# RaspberryMicroSD.net
KiCad netlist of a schematic drawn in Altium Designer
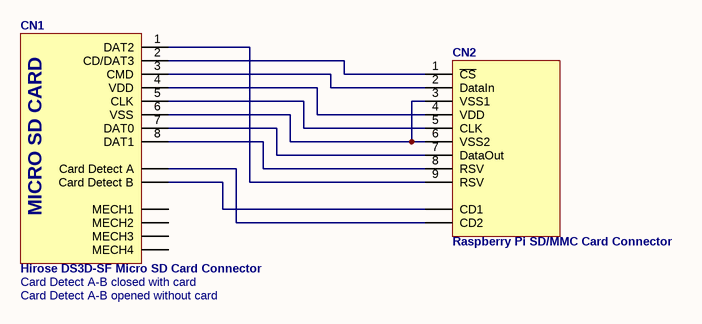
[diagram p0: RaspberryMicroSD.SchDoc]

(export (version "E")
  (design (tool "Eeschema 10.0.6"))
  (components
    (comp (ref "CN1")
      (value "Hirose DS3D-SF Micro SD Card Connector")
      (footprint "DM3D-SF")
      (description "DM3D Micro SD, Push-Pull (no ejection mechanism) Card Connector")
      (libsource (lib "data_cards") (part "DM3D-SF"))
    )
    (comp (ref "CN2")
      (value "Raspberry Pi SD/MMC Card Connector")
      (footprint "PCBComponent_1")
      (description "SD/MMC Card Connector")
      (libsource (lib "data_cards") (part "SD/MMC_1"))
    )
  )
  (nets
    (net (code "1") (name "Net-(CN1-CD{slash}DAT3)") (class "Default")
      (node (ref "CN1") (pin "2") (pinfunction "CD/DAT3_2") (pintype "passive"))
      (node (ref "CN2") (pin "1") (pinfunction "~{CS}_1") (pintype "passive"))
    )
    (net (code "2") (name "Net-(CN1-CLK)") (class "Default")
      (node (ref "CN1") (pin "5") (pinfunction "CLK_5") (pintype "passive"))
      (node (ref "CN2") (pin "5") (pinfunction "CLK_5") (pintype "passive"))
    )
    (net (code "3") (name "Net-(CN1-CMD)") (class "Default")
      (node (ref "CN1") (pin "3") (pinfunction "CMD_3") (pintype "passive"))
      (node (ref "CN2") (pin "2") (pinfunction "DataIn_2") (pintype "passive"))
    )
    (net (code "4") (name "Net-(CN1-Card_Detect_A)") (class "Default")
      (node (ref "CN1") (pin "CD1") (pinfunction "Card_Detect_A_CD1") (pintype "passive"))
      (node (ref "CN2") (pin "CD2") (pinfunction "CD2_CD2") (pintype "passive"))
    )
    (net (code "5") (name "Net-(CN1-Card_Detect_B)") (class "Default")
      (node (ref "CN1") (pin "CD2") (pinfunction "Card_Detect_B_CD2") (pintype "passive"))
      (node (ref "CN2") (pin "CD1") (pinfunction "CD1_CD1") (pintype "passive"))
    )
    (net (code "6") (name "Net-(CN1-DAT0)") (class "Default")
      (node (ref "CN1") (pin "7") (pinfunction "DAT0_7") (pintype "passive"))
      (node (ref "CN2") (pin "7") (pinfunction "DataOut_7") (pintype "passive"))
    )
    (net (code "7") (name "Net-(CN1-DAT1)") (class "Default")
      (node (ref "CN1") (pin "8") (pinfunction "DAT1_8") (pintype "passive"))
      (node (ref "CN2") (pin "8") (pinfunction "RSV_8") (pintype "passive"))
    )
    (net (code "8") (name "Net-(CN1-DAT2)") (class "Default")
      (node (ref "CN1") (pin "1") (pinfunction "DAT2_1") (pintype "passive"))
      (node (ref "CN2") (pin "9") (pinfunction "RSV_9") (pintype "passive"))
    )
    (net (code "9") (name "Net-(CN1-VDD)") (class "Default")
      (node (ref "CN1") (pin "4") (pinfunction "VDD_4") (pintype "passive"))
      (node (ref "CN2") (pin "4") (pinfunction "VDD_4") (pintype "passive"))
    )
    (net (code "10") (name "Net-(CN1-VSS)") (class "Default")
      (node (ref "CN1") (pin "6") (pinfunction "VSS_6") (pintype "passive"))
      (node (ref "CN2") (pin "3") (pinfunction "VSS1_3") (pintype "passive"))
      (node (ref "CN2") (pin "6") (pinfunction "VSS2_6") (pintype "passive"))
    )
    (net (code "11") (name "unconnected-(CN1-MECH1-PadMech1)") (class "Default")
      (node (ref "CN1") (pin "Mech1") (pinfunction "MECH1_Mech1") (pintype "passive"))
    )
    (net (code "12") (name "unconnected-(CN1-MECH2-PadMech2)") (class "Default")
      (node (ref "CN1") (pin "Mech2") (pinfunction "MECH2_Mech2") (pintype "passive"))
    )
    (net (code "13") (name "unconnected-(CN1-MECH3-PadMech3)") (class "Default")
      (node (ref "CN1") (pin "Mech3") (pinfunction "MECH3_Mech3") (pintype "passive"))
    )
    (net (code "14") (name "unconnected-(CN1-MECH4-PadMech4)") (class "Default")
      (node (ref "CN1") (pin "Mech4") (pinfunction "MECH4_Mech4") (pintype "passive"))
    )
  )
)
